# 7130mod.net
KiCad netlist of a schematic drawn in EAGLE
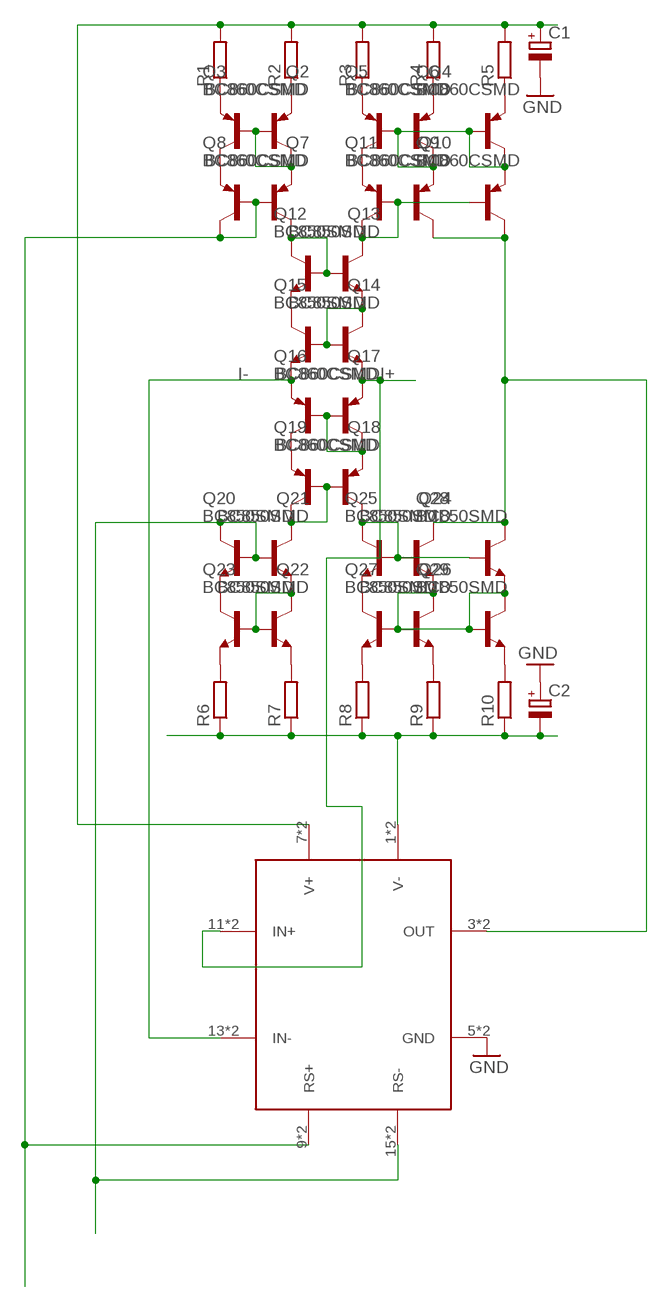
[diagram p0: schematic, sheet 1]

(export (version "E")
  (design (tool "Eeschema 10.0.6"))
  (components
    (comp (ref "C1")
      (value "CPOL-EUSP-CAP-CX")
      (footprint "eagle-import:SP-CAP-CX")
      (libsource (lib "eagle-import") (part "CPOL-EUSP-CAP-CX"))
    )
    (comp (ref "C2")
      (value "CPOL-EUSP-CAP-CX")
      (footprint "eagle-import:SP-CAP-CX")
      (libsource (lib "eagle-import") (part "CPOL-EUSP-CAP-CX"))
    )
    (comp (ref "Q2")
      (value "BC860CSMD")
      (footprint "eagle-import:SOT23-BEC")
      (libsource (lib "eagle-import") (part "BC860SMDC"))
    )
    (comp (ref "Q3")
      (value "BC860CSMD")
      (footprint "eagle-import:SOT23-BEC")
      (libsource (lib "eagle-import") (part "BC860SMDC"))
    )
    (comp (ref "Q4")
      (value "BC860CSMD")
      (footprint "eagle-import:SOT23-BEC")
      (libsource (lib "eagle-import") (part "BC860SMDC"))
    )
    (comp (ref "Q5")
      (value "BC860CSMD")
      (footprint "eagle-import:SOT23-BEC")
      (libsource (lib "eagle-import") (part "BC860SMDC"))
    )
    (comp (ref "Q6")
      (value "BC860CSMD")
      (footprint "eagle-import:SOT23-BEC")
      (libsource (lib "eagle-import") (part "BC860SMDC"))
    )
    (comp (ref "Q7")
      (value "BC860CSMD")
      (footprint "eagle-import:SOT23-BEC")
      (libsource (lib "eagle-import") (part "BC860SMDC"))
    )
    (comp (ref "Q8")
      (value "BC860CSMD")
      (footprint "eagle-import:SOT23-BEC")
      (libsource (lib "eagle-import") (part "BC860SMDC"))
    )
    (comp (ref "Q9")
      (value "BC860CSMD")
      (footprint "eagle-import:SOT23-BEC")
      (libsource (lib "eagle-import") (part "BC860SMDC"))
    )
    (comp (ref "Q10")
      (value "BC860CSMD")
      (footprint "eagle-import:SOT23-BEC")
      (libsource (lib "eagle-import") (part "BC860SMDC"))
    )
    (comp (ref "Q11")
      (value "BC860CSMD")
      (footprint "eagle-import:SOT23-BEC")
      (libsource (lib "eagle-import") (part "BC860SMDC"))
    )
    (comp (ref "Q12")
      (value "BC850SMD")
      (footprint "eagle-import:SOT23-BEC")
      (libsource (lib "eagle-import") (part "BC850SMD"))
    )
    (comp (ref "Q13")
      (value "BC850SMD")
      (footprint "eagle-import:SOT23-BEC")
      (libsource (lib "eagle-import") (part "BC850SMD"))
    )
    (comp (ref "Q14")
      (value "BC850SMD")
      (footprint "eagle-import:SOT23-BEC")
      (libsource (lib "eagle-import") (part "BC850SMD"))
    )
    (comp (ref "Q15")
      (value "BC850SMD")
      (footprint "eagle-import:SOT23-BEC")
      (libsource (lib "eagle-import") (part "BC850SMD"))
    )
    (comp (ref "Q16")
      (value "BC860CSMD")
      (footprint "eagle-import:SOT23-BEC")
      (libsource (lib "eagle-import") (part "BC860SMDC"))
    )
    (comp (ref "Q17")
      (value "BC860CSMD")
      (footprint "eagle-import:SOT23-BEC")
      (libsource (lib "eagle-import") (part "BC860SMDC"))
    )
    (comp (ref "Q18")
      (value "BC860CSMD")
      (footprint "eagle-import:SOT23-BEC")
      (libsource (lib "eagle-import") (part "BC860SMDC"))
    )
    (comp (ref "Q19")
      (value "BC860CSMD")
      (footprint "eagle-import:SOT23-BEC")
      (libsource (lib "eagle-import") (part "BC860SMDC"))
    )
    (comp (ref "Q20")
      (value "BC850SMD")
      (footprint "eagle-import:SOT23-BEC")
      (libsource (lib "eagle-import") (part "BC850SMD"))
    )
    (comp (ref "Q21")
      (value "BC850SMD")
      (footprint "eagle-import:SOT23-BEC")
      (libsource (lib "eagle-import") (part "BC850SMD"))
    )
    (comp (ref "Q22")
      (value "BC850SMD")
      (footprint "eagle-import:SOT23-BEC")
      (libsource (lib "eagle-import") (part "BC850SMD"))
    )
    (comp (ref "Q23")
      (value "BC850SMD")
      (footprint "eagle-import:SOT23-BEC")
      (libsource (lib "eagle-import") (part "BC850SMD"))
    )
    (comp (ref "Q24")
      (value "BC850SMD")
      (footprint "eagle-import:SOT23-BEC")
      (libsource (lib "eagle-import") (part "BC850SMD"))
    )
    (comp (ref "Q25")
      (value "BC850SMD")
      (footprint "eagle-import:SOT23-BEC")
      (libsource (lib "eagle-import") (part "BC850SMD"))
    )
    (comp (ref "Q26")
      (value "BC850SMD")
      (footprint "eagle-import:SOT23-BEC")
      (libsource (lib "eagle-import") (part "BC850SMD"))
    )
    (comp (ref "Q27")
      (value "BC850SMD")
      (footprint "eagle-import:SOT23-BEC")
      (libsource (lib "eagle-import") (part "BC850SMD"))
    )
    (comp (ref "Q28")
      (value "BC850SMD")
      (footprint "eagle-import:SOT23-BEC")
      (libsource (lib "eagle-import") (part "BC850SMD"))
    )
    (comp (ref "Q29")
      (value "BC850SMD")
      (footprint "eagle-import:SOT23-BEC")
      (libsource (lib "eagle-import") (part "BC850SMD"))
    )
    (comp (ref "R1")
      (value "R-EU_R0805")
      (footprint "eagle-import:R0805")
      (libsource (lib "eagle-import") (part "R-EU_R0805"))
    )
    (comp (ref "R2")
      (value "R-EU_R0805")
      (footprint "eagle-import:R0805")
      (libsource (lib "eagle-import") (part "R-EU_R0805"))
    )
    (comp (ref "R3")
      (value "R-EU_R0805")
      (footprint "eagle-import:R0805")
      (libsource (lib "eagle-import") (part "R-EU_R0805"))
    )
    (comp (ref "R4")
      (value "R-EU_R0805")
      (footprint "eagle-import:R0805")
      (libsource (lib "eagle-import") (part "R-EU_R0805"))
    )
    (comp (ref "R5")
      (value "R-EU_R0805")
      (footprint "eagle-import:R0805")
      (libsource (lib "eagle-import") (part "R-EU_R0805"))
    )
    (comp (ref "R6")
      (value "R-EU_R0805")
      (footprint "eagle-import:R0805")
      (libsource (lib "eagle-import") (part "R-EU_R0805"))
    )
    (comp (ref "R7")
      (value "R-EU_R0805")
      (footprint "eagle-import:R0805")
      (libsource (lib "eagle-import") (part "R-EU_R0805"))
    )
    (comp (ref "R8")
      (value "R-EU_R0805")
      (footprint "eagle-import:R0805")
      (libsource (lib "eagle-import") (part "R-EU_R0805"))
    )
    (comp (ref "R9")
      (value "R-EU_R0805")
      (footprint "eagle-import:R0805")
      (libsource (lib "eagle-import") (part "R-EU_R0805"))
    )
    (comp (ref "R10")
      (value "R-EU_R0805")
      (footprint "eagle-import:R0805")
      (libsource (lib "eagle-import") (part "R-EU_R0805"))
    )
    (comp (ref "U$1")
      (value "7130MOD")
      (footprint "eagle-import:7130MOD")
      (libsource (lib "eagle-import") (part "7130MOD"))
    )
  )
  (nets
    (net (code "1") (name "/I+") (class "Default")
      (node (ref "Q15") (pin "E") (pinfunction "E_E") (pintype "passive"))
      (node (ref "Q16") (pin "E") (pinfunction "E_E") (pintype "passive"))
      (node (ref "U$1") (pin "11") (pinfunction "IN+_11") (pintype "bidirectional"))
      (node (ref "U$1") (pin "12") (pinfunction "IN+_12") (pintype "bidirectional"))
    )
    (net (code "2") (name "/I-") (class "Default")
      (node (ref "Q14") (pin "E") (pinfunction "E_E") (pintype "passive"))
      (node (ref "Q17") (pin "E") (pinfunction "E_E") (pintype "passive"))
      (node (ref "U$1") (pin "13") (pinfunction "IN-_13") (pintype "bidirectional"))
      (node (ref "U$1") (pin "14") (pinfunction "IN-_14") (pintype "bidirectional"))
    )
    (net (code "3") (name "GND") (class "Default")
      (node (ref "C1") (pin "-") (pinfunction "-_-") (pintype "passive"))
      (node (ref "C2") (pin "+") (pinfunction "+_+") (pintype "passive"))
      (node (ref "U$1") (pin "5") (pinfunction "GND_5") (pintype "bidirectional"))
      (node (ref "U$1") (pin "6") (pinfunction "GND_6") (pintype "bidirectional"))
    )
    (net (code "4") (name "Net-(C1-Pad+)") (class "Default")
      (node (ref "C1") (pin "+") (pinfunction "+_+") (pintype "passive"))
      (node (ref "R1") (pin "2") (pinfunction "2_2") (pintype "passive"))
      (node (ref "R2") (pin "2") (pinfunction "2_2") (pintype "passive"))
      (node (ref "R3") (pin "2") (pinfunction "2_2") (pintype "passive"))
      (node (ref "R4") (pin "2") (pinfunction "2_2") (pintype "passive"))
      (node (ref "R5") (pin "2") (pinfunction "2_2") (pintype "passive"))
      (node (ref "U$1") (pin "7") (pinfunction "V+_7") (pintype "bidirectional"))
      (node (ref "U$1") (pin "8") (pinfunction "V+_8") (pintype "bidirectional"))
    )
    (net (code "5") (name "Net-(C2-Pad-)") (class "Default")
      (node (ref "C2") (pin "-") (pinfunction "-_-") (pintype "passive"))
      (node (ref "R10") (pin "1") (pinfunction "1_1") (pintype "passive"))
      (node (ref "R6") (pin "1") (pinfunction "1_1") (pintype "passive"))
      (node (ref "R7") (pin "1") (pinfunction "1_1") (pintype "passive"))
      (node (ref "R8") (pin "1") (pinfunction "1_1") (pintype "passive"))
      (node (ref "R9") (pin "1") (pinfunction "1_1") (pintype "passive"))
      (node (ref "U$1") (pin "1") (pinfunction "V-_1") (pintype "bidirectional"))
      (node (ref "U$1") (pin "2") (pinfunction "V-_2") (pintype "bidirectional"))
    )
    (net (code "6") (name "Net-(Q2-PadB)") (class "Default")
      (node (ref "Q2") (pin "B") (pinfunction "B_B") (pintype "passive"))
      (node (ref "Q3") (pin "B") (pinfunction "B_B") (pintype "passive"))
      (node (ref "Q3") (pin "C") (pinfunction "C_C") (pintype "passive"))
      (node (ref "Q8") (pin "E") (pinfunction "E_E") (pintype "passive"))
    )
    (net (code "7") (name "Net-(Q2-PadC)") (class "Default")
      (node (ref "Q2") (pin "C") (pinfunction "C_C") (pintype "passive"))
      (node (ref "Q7") (pin "E") (pinfunction "E_E") (pintype "passive"))
    )
    (net (code "8") (name "Net-(Q2-PadE)") (class "Default")
      (node (ref "Q2") (pin "E") (pinfunction "E_E") (pintype "passive"))
      (node (ref "R1") (pin "1") (pinfunction "1_1") (pintype "passive"))
    )
    (net (code "9") (name "Net-(Q3-PadE)") (class "Default")
      (node (ref "Q3") (pin "E") (pinfunction "E_E") (pintype "passive"))
      (node (ref "R2") (pin "1") (pinfunction "1_1") (pintype "passive"))
    )
    (net (code "10") (name "Net-(Q4-PadE)") (class "Default")
      (node (ref "Q4") (pin "E") (pinfunction "E_E") (pintype "passive"))
      (node (ref "R3") (pin "1") (pinfunction "1_1") (pintype "passive"))
    )
    (net (code "11") (name "Net-(Q5-PadE)") (class "Default")
      (node (ref "Q5") (pin "E") (pinfunction "E_E") (pintype "passive"))
      (node (ref "R4") (pin "1") (pinfunction "1_1") (pintype "passive"))
    )
    (net (code "12") (name "Net-(Q6-PadE)") (class "Default")
      (node (ref "Q6") (pin "E") (pinfunction "E_E") (pintype "passive"))
      (node (ref "R5") (pin "1") (pinfunction "1_1") (pintype "passive"))
    )
    (net (code "13") (name "Net-(Q7-PadB)") (class "Default")
      (node (ref "Q7") (pin "B") (pinfunction "B_B") (pintype "passive"))
      (node (ref "Q7") (pin "C") (pinfunction "C_C") (pintype "passive"))
      (node (ref "Q8") (pin "B") (pinfunction "B_B") (pintype "passive"))
      (node (ref "U$1") (pin "10") (pinfunction "RS+_10") (pintype "bidirectional"))
      (node (ref "U$1") (pin "9") (pinfunction "RS+_9") (pintype "bidirectional"))
    )
    (net (code "14") (name "Net-(Q10-PadB)") (class "Default")
      (node (ref "Q10") (pin "B") (pinfunction "B_B") (pintype "passive"))
      (node (ref "Q10") (pin "C") (pinfunction "C_C") (pintype "passive"))
      (node (ref "Q11") (pin "B") (pinfunction "B_B") (pintype "passive"))
      (node (ref "Q12") (pin "C") (pinfunction "C_C") (pintype "passive"))
      (node (ref "Q9") (pin "B") (pinfunction "B_B") (pintype "passive"))
    )
    (net (code "15") (name "Net-(Q10-PadE)") (class "Default")
      (node (ref "Q10") (pin "E") (pinfunction "E_E") (pintype "passive"))
      (node (ref "Q4") (pin "C") (pinfunction "C_C") (pintype "passive"))
    )
    (net (code "16") (name "Net-(Q11-PadC)") (class "Default")
      (node (ref "Q11") (pin "C") (pinfunction "C_C") (pintype "passive"))
      (node (ref "Q25") (pin "C") (pinfunction "C_C") (pintype "passive"))
      (node (ref "Q28") (pin "C") (pinfunction "C_C") (pintype "passive"))
      (node (ref "Q9") (pin "C") (pinfunction "C_C") (pintype "passive"))
      (node (ref "U$1") (pin "3") (pinfunction "OUT_3") (pintype "bidirectional"))
      (node (ref "U$1") (pin "4") (pinfunction "OUT_4") (pintype "bidirectional"))
    )
    (net (code "17") (name "Net-(Q11-PadE)") (class "Default")
      (node (ref "Q11") (pin "E") (pinfunction "E_E") (pintype "passive"))
      (node (ref "Q4") (pin "B") (pinfunction "B_B") (pintype "passive"))
      (node (ref "Q5") (pin "B") (pinfunction "B_B") (pintype "passive"))
      (node (ref "Q5") (pin "C") (pinfunction "C_C") (pintype "passive"))
      (node (ref "Q6") (pin "B") (pinfunction "B_B") (pintype "passive"))
      (node (ref "Q6") (pin "C") (pinfunction "C_C") (pintype "passive"))
      (node (ref "Q9") (pin "E") (pinfunction "E_E") (pintype "passive"))
    )
    (net (code "18") (name "Net-(Q12-PadB)") (class "Default")
      (node (ref "Q12") (pin "B") (pinfunction "B_B") (pintype "passive"))
      (node (ref "Q13") (pin "B") (pinfunction "B_B") (pintype "passive"))
      (node (ref "Q13") (pin "C") (pinfunction "C_C") (pintype "passive"))
      (node (ref "Q8") (pin "C") (pinfunction "C_C") (pintype "passive"))
    )
    (net (code "19") (name "Net-(Q12-PadE)") (class "Default")
      (node (ref "Q12") (pin "E") (pinfunction "E_E") (pintype "passive"))
      (node (ref "Q14") (pin "B") (pinfunction "B_B") (pintype "passive"))
      (node (ref "Q15") (pin "B") (pinfunction "B_B") (pintype "passive"))
      (node (ref "Q15") (pin "C") (pinfunction "C_C") (pintype "passive"))
    )
    (net (code "20") (name "Net-(Q13-PadE)") (class "Default")
      (node (ref "Q13") (pin "E") (pinfunction "E_E") (pintype "passive"))
      (node (ref "Q14") (pin "C") (pinfunction "C_C") (pintype "passive"))
    )
    (net (code "21") (name "Net-(Q16-PadB)") (class "Default")
      (node (ref "Q16") (pin "B") (pinfunction "B_B") (pintype "passive"))
      (node (ref "Q16") (pin "C") (pinfunction "C_C") (pintype "passive"))
      (node (ref "Q17") (pin "B") (pinfunction "B_B") (pintype "passive"))
      (node (ref "Q19") (pin "E") (pinfunction "E_E") (pintype "passive"))
    )
    (net (code "22") (name "Net-(Q17-PadC)") (class "Default")
      (node (ref "Q17") (pin "C") (pinfunction "C_C") (pintype "passive"))
      (node (ref "Q18") (pin "E") (pinfunction "E_E") (pintype "passive"))
    )
    (net (code "23") (name "Net-(Q18-PadB)") (class "Default")
      (node (ref "Q18") (pin "B") (pinfunction "B_B") (pintype "passive"))
      (node (ref "Q18") (pin "C") (pinfunction "C_C") (pintype "passive"))
      (node (ref "Q19") (pin "B") (pinfunction "B_B") (pintype "passive"))
      (node (ref "Q20") (pin "C") (pinfunction "C_C") (pintype "passive"))
    )
    (net (code "24") (name "Net-(Q19-PadC)") (class "Default")
      (node (ref "Q19") (pin "C") (pinfunction "C_C") (pintype "passive"))
      (node (ref "Q24") (pin "B") (pinfunction "B_B") (pintype "passive"))
      (node (ref "Q24") (pin "C") (pinfunction "C_C") (pintype "passive"))
      (node (ref "Q25") (pin "B") (pinfunction "B_B") (pintype "passive"))
      (node (ref "Q28") (pin "B") (pinfunction "B_B") (pintype "passive"))
    )
    (net (code "25") (name "Net-(Q20-PadB)") (class "Default")
      (node (ref "Q20") (pin "B") (pinfunction "B_B") (pintype "passive"))
      (node (ref "Q21") (pin "B") (pinfunction "B_B") (pintype "passive"))
      (node (ref "Q21") (pin "C") (pinfunction "C_C") (pintype "passive"))
      (node (ref "U$1") (pin "15") (pinfunction "RS-_15") (pintype "bidirectional"))
      (node (ref "U$1") (pin "16") (pinfunction "RS-_16") (pintype "bidirectional"))
    )
    (net (code "26") (name "Net-(Q20-PadE)") (class "Default")
      (node (ref "Q20") (pin "E") (pinfunction "E_E") (pintype "passive"))
      (node (ref "Q22") (pin "B") (pinfunction "B_B") (pintype "passive"))
      (node (ref "Q23") (pin "B") (pinfunction "B_B") (pintype "passive"))
      (node (ref "Q23") (pin "C") (pinfunction "C_C") (pintype "passive"))
    )
    (net (code "27") (name "Net-(Q21-PadE)") (class "Default")
      (node (ref "Q21") (pin "E") (pinfunction "E_E") (pintype "passive"))
      (node (ref "Q22") (pin "C") (pinfunction "C_C") (pintype "passive"))
    )
    (net (code "28") (name "Net-(Q22-PadE)") (class "Default")
      (node (ref "Q22") (pin "E") (pinfunction "E_E") (pintype "passive"))
      (node (ref "R6") (pin "2") (pinfunction "2_2") (pintype "passive"))
    )
    (net (code "29") (name "Net-(Q23-PadE)") (class "Default")
      (node (ref "Q23") (pin "E") (pinfunction "E_E") (pintype "passive"))
      (node (ref "R7") (pin "2") (pinfunction "2_2") (pintype "passive"))
    )
    (net (code "30") (name "Net-(Q24-PadE)") (class "Default")
      (node (ref "Q24") (pin "E") (pinfunction "E_E") (pintype "passive"))
      (node (ref "Q26") (pin "C") (pinfunction "C_C") (pintype "passive"))
    )
    (net (code "31") (name "Net-(Q25-PadE)") (class "Default")
      (node (ref "Q25") (pin "E") (pinfunction "E_E") (pintype "passive"))
      (node (ref "Q26") (pin "B") (pinfunction "B_B") (pintype "passive"))
      (node (ref "Q27") (pin "B") (pinfunction "B_B") (pintype "passive"))
      (node (ref "Q27") (pin "C") (pinfunction "C_C") (pintype "passive"))
      (node (ref "Q28") (pin "E") (pinfunction "E_E") (pintype "passive"))
      (node (ref "Q29") (pin "B") (pinfunction "B_B") (pintype "passive"))
      (node (ref "Q29") (pin "C") (pinfunction "C_C") (pintype "passive"))
    )
    (net (code "32") (name "Net-(Q26-PadE)") (class "Default")
      (node (ref "Q26") (pin "E") (pinfunction "E_E") (pintype "passive"))
      (node (ref "R8") (pin "2") (pinfunction "2_2") (pintype "passive"))
    )
    (net (code "33") (name "Net-(Q27-PadE)") (class "Default")
      (node (ref "Q27") (pin "E") (pinfunction "E_E") (pintype "passive"))
      (node (ref "R9") (pin "2") (pinfunction "2_2") (pintype "passive"))
    )
    (net (code "34") (name "Net-(Q29-PadE)") (class "Default")
      (node (ref "Q29") (pin "E") (pinfunction "E_E") (pintype "passive"))
      (node (ref "R10") (pin "2") (pinfunction "2_2") (pintype "passive"))
    )
  )
)
